# USB_IFC.net
KiCad netlist of a schematic drawn in Altium Designer
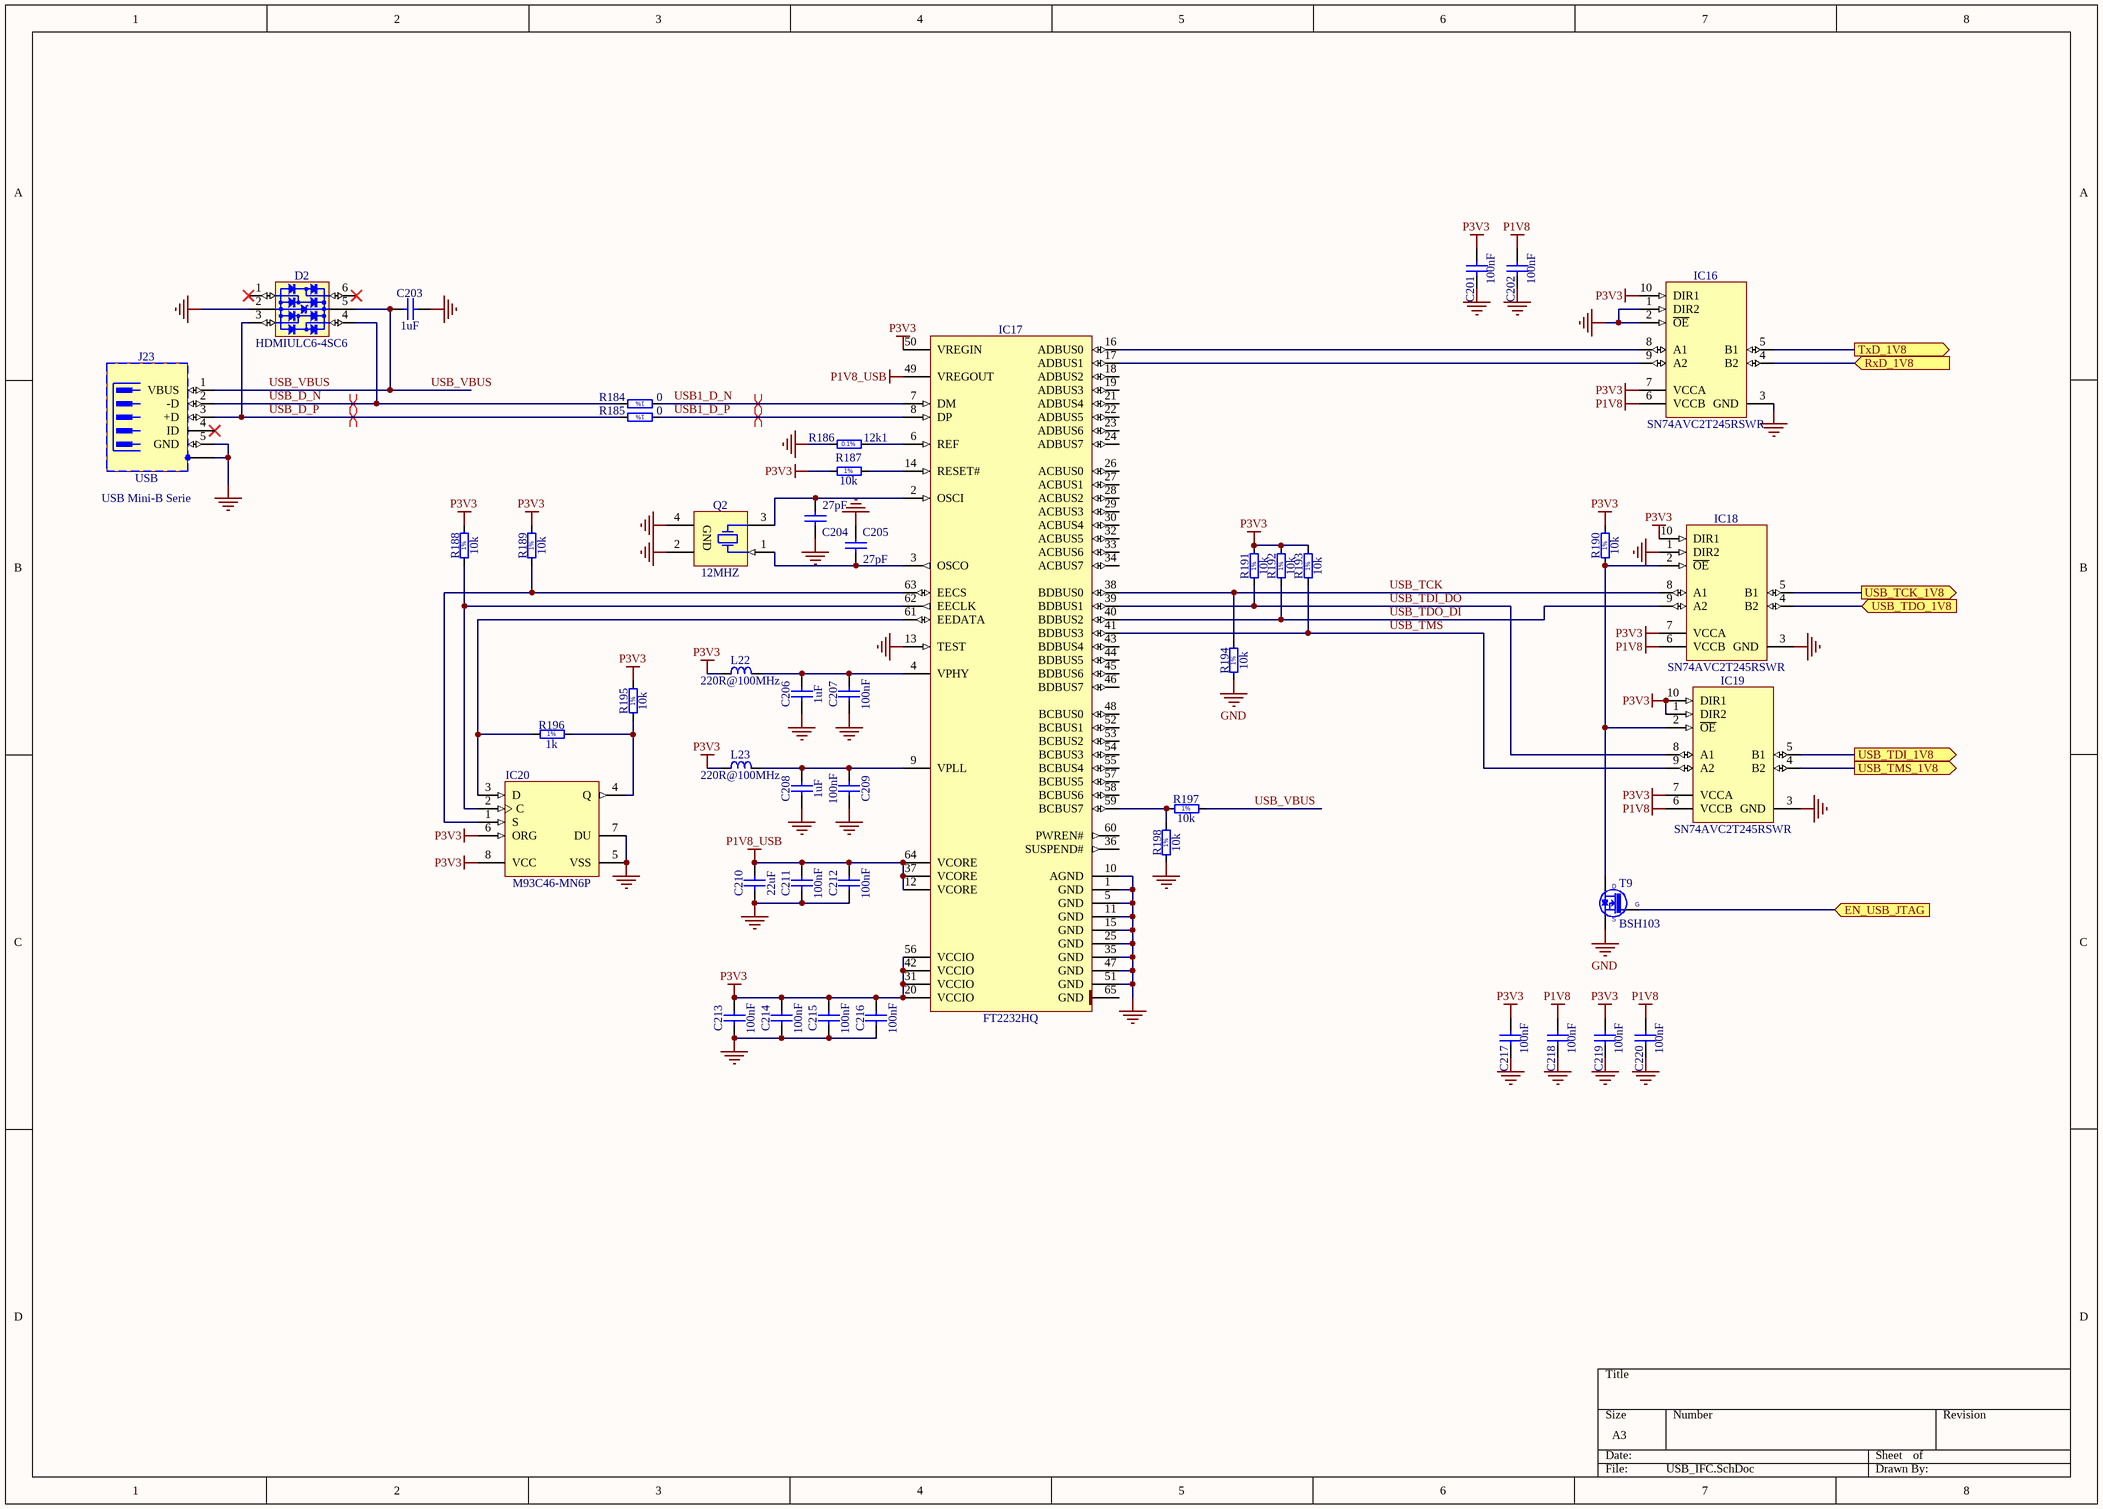
[diagram p0: USB_IFC.SchDoc]

(export (version "E")
  (design (tool "Eeschema 10.0.6"))
  (components
    (comp (ref "C201")
      (value "100nF")
      (footprint "CAPC0603X33N")
      (description "Non-polarised capacitor")
      (fields
        (field (name "PART NUMBER") "CC0201_100NF_6.3V_10%_X5R")
        (field (name "VOLTAGE") "6.3V")
        (field (name "AUTHOR") "CERN DEM JLC")
      )
      (libsource (lib "Capacitors") (part "Capacitor - non polarized"))
    )
    (comp (ref "C202")
      (value "100nF")
      (footprint "CAPC0603X33N")
      (description "Non-polarised capacitor")
      (fields
        (field (name "PART NUMBER") "CC0201_100NF_6.3V_10%_X5R")
        (field (name "VOLTAGE") "6.3V")
        (field (name "AUTHOR") "CERN DEM JLC")
      )
      (libsource (lib "Capacitors") (part "Capacitor - non polarized"))
    )
    (comp (ref "C203")
      (value "1uF")
      (footprint "CAPC1005X55N")
      (description "Non-polarised capacitor")
      (fields
        (field (name "PART NUMBER") "CC0402_1UF_16V_10%_X5R")
        (field (name "VOLTAGE") "16V")
        (field (name "AUTHOR") "CERN DEM JLC")
      )
      (libsource (lib "Capacitors") (part "Capacitor - non polarized"))
    )
    (comp (ref "C204")
      (value "27pF")
      (footprint "CAPC1608X87N")
      (description "Non-polarised capacitor")
      (fields
        (field (name "PART NUMBER") "CC0603_27PF_50V_5%_NP0")
        (field (name "VOLTAGE") "50V")
        (field (name "AUTHOR") "CERN DEM JLC")
      )
      (libsource (lib "Capacitors") (part "Capacitor - non polarized"))
    )
    (comp (ref "C205")
      (value "27pF")
      (footprint "CAPC1608X87N")
      (description "Non-polarised capacitor")
      (fields
        (field (name "PART NUMBER") "CC0603_27PF_50V_5%_NP0")
        (field (name "VOLTAGE") "50V")
        (field (name "AUTHOR") "CERN DEM JLC")
      )
      (libsource (lib "Capacitors") (part "Capacitor - non polarized"))
    )
    (comp (ref "C206")
      (value "1uF")
      (footprint "CAPC1005X55N")
      (description "Non-polarised capacitor")
      (fields
        (field (name "PART NUMBER") "CC0402_1UF_16V_10%_X5R")
        (field (name "VOLTAGE") "16V")
        (field (name "AUTHOR") "CERN DEM JLC")
      )
      (libsource (lib "Capacitors") (part "Capacitor - non polarized"))
    )
    (comp (ref "C207")
      (value "100nF")
      (footprint "CAPC0603X33N")
      (description "Non-polarised capacitor")
      (fields
        (field (name "PART NUMBER") "CC0201_100NF_6.3V_10%_X5R")
        (field (name "VOLTAGE") "6.3V")
        (field (name "AUTHOR") "CERN DEM JLC")
      )
      (libsource (lib "Capacitors") (part "Capacitor - non polarized"))
    )
    (comp (ref "C208")
      (value "1uF")
      (footprint "CAPC1005X55N")
      (description "Non-polarised capacitor")
      (fields
        (field (name "PART NUMBER") "CC0402_1UF_16V_10%_X5R")
        (field (name "VOLTAGE") "16V")
        (field (name "AUTHOR") "CERN DEM JLC")
      )
      (libsource (lib "Capacitors") (part "Capacitor - non polarized"))
    )
    (comp (ref "C209")
      (value "100nF")
      (footprint "CAPC0603X33N")
      (description "Non-polarised capacitor")
      (fields
        (field (name "PART NUMBER") "CC0201_100NF_6.3V_10%_X5R")
        (field (name "VOLTAGE") "6.3V")
        (field (name "AUTHOR") "CERN DEM JLC")
      )
      (libsource (lib "Capacitors") (part "Capacitor - non polarized"))
    )
    (comp (ref "C210")
      (value "22uF")
      (footprint "CAPC2012X135N")
      (description "Non-polarised capacitor")
      (fields
        (field (name "PART NUMBER") "CC0805_22UF_6.3V_20%_X5R")
        (field (name "VOLTAGE") "6.3V")
        (field (name "AUTHOR") "CERN DEM JLC")
      )
      (libsource (lib "Capacitors") (part "Capacitor - non polarized"))
    )
    (comp (ref "C211")
      (value "100nF")
      (footprint "CAPC0603X33N")
      (description "Non-polarised capacitor")
      (fields
        (field (name "PART NUMBER") "CC0201_100NF_6.3V_10%_X5R")
        (field (name "VOLTAGE") "6.3V")
        (field (name "AUTHOR") "CERN DEM JLC")
      )
      (libsource (lib "Capacitors") (part "Capacitor - non polarized"))
    )
    (comp (ref "C212")
      (value "100nF")
      (footprint "CAPC0603X33N")
      (description "Non-polarised capacitor")
      (fields
        (field (name "PART NUMBER") "CC0201_100NF_6.3V_10%_X5R")
        (field (name "VOLTAGE") "6.3V")
        (field (name "AUTHOR") "CERN DEM JLC")
      )
      (libsource (lib "Capacitors") (part "Capacitor - non polarized"))
    )
    (comp (ref "C213")
      (value "100nF")
      (footprint "CAPC0603X33N")
      (description "Non-polarised capacitor")
      (fields
        (field (name "PART NUMBER") "CC0201_100NF_6.3V_10%_X5R")
        (field (name "VOLTAGE") "6.3V")
        (field (name "AUTHOR") "CERN DEM JLC")
      )
      (libsource (lib "Capacitors") (part "Capacitor - non polarized"))
    )
    (comp (ref "C214")
      (value "100nF")
      (footprint "CAPC0603X33N")
      (description "Non-polarised capacitor")
      (fields
        (field (name "PART NUMBER") "CC0201_100NF_6.3V_10%_X5R")
        (field (name "VOLTAGE") "6.3V")
        (field (name "AUTHOR") "CERN DEM JLC")
      )
      (libsource (lib "Capacitors") (part "Capacitor - non polarized"))
    )
    (comp (ref "C215")
      (value "100nF")
      (footprint "CAPC0603X33N")
      (description "Non-polarised capacitor")
      (fields
        (field (name "PART NUMBER") "CC0201_100NF_6.3V_10%_X5R")
        (field (name "VOLTAGE") "6.3V")
        (field (name "AUTHOR") "CERN DEM JLC")
      )
      (libsource (lib "Capacitors") (part "Capacitor - non polarized"))
    )
    (comp (ref "C216")
      (value "100nF")
      (footprint "CAPC0603X33N")
      (description "Non-polarised capacitor")
      (fields
        (field (name "PART NUMBER") "CC0201_100NF_6.3V_10%_X5R")
        (field (name "VOLTAGE") "6.3V")
        (field (name "AUTHOR") "CERN DEM JLC")
      )
      (libsource (lib "Capacitors") (part "Capacitor - non polarized"))
    )
    (comp (ref "C217")
      (value "100nF")
      (footprint "CAPC0603X33N")
      (description "Non-polarised capacitor")
      (fields
        (field (name "PART NUMBER") "CC0201_100NF_6.3V_10%_X5R")
        (field (name "VOLTAGE") "6.3V")
        (field (name "AUTHOR") "CERN DEM JLC")
      )
      (libsource (lib "Capacitors") (part "Capacitor - non polarized"))
    )
    (comp (ref "C218")
      (value "100nF")
      (footprint "CAPC0603X33N")
      (description "Non-polarised capacitor")
      (fields
        (field (name "PART NUMBER") "CC0201_100NF_6.3V_10%_X5R")
        (field (name "VOLTAGE") "6.3V")
        (field (name "AUTHOR") "CERN DEM JLC")
      )
      (libsource (lib "Capacitors") (part "Capacitor - non polarized"))
    )
    (comp (ref "C219")
      (value "100nF")
      (footprint "CAPC0603X33N")
      (description "Non-polarised capacitor")
      (fields
        (field (name "PART NUMBER") "CC0201_100NF_6.3V_10%_X5R")
        (field (name "VOLTAGE") "6.3V")
        (field (name "AUTHOR") "CERN DEM JLC")
      )
      (libsource (lib "Capacitors") (part "Capacitor - non polarized"))
    )
    (comp (ref "C220")
      (value "100nF")
      (footprint "CAPC0603X33N")
      (description "Non-polarised capacitor")
      (fields
        (field (name "PART NUMBER") "CC0201_100NF_6.3V_10%_X5R")
        (field (name "VOLTAGE") "6.3V")
        (field (name "AUTHOR") "CERN DEM JLC")
      )
      (libsource (lib "Capacitors") (part "Capacitor - non polarized"))
    )
    (comp (ref "D2")
      (value "HDMIULC6-4SC6")
      (footprint "SOT95P280X145-6N")
      (description "Ultra Large Bandwidth HDMI ESD Protection")
      (fields
        (field (name "VOLTAGE") "6V")
        (field (name "MANUFACTURER") "ST MICROELECTRONICS")
        (field (name "AUTHOR") "CERN DEM JLC")
      )
      (libsource (lib "ICs And Semiconductors") (part "HDMIULC6-4SC6"))
    )
    (comp (ref "IC16")
      (value "SN74AVC2T245RSWR")
      (footprint "QFN40P140X180X55-10N")
      (description "Dual-Bit Dual-Supply Bus Transceiver With Configurable Voltage Translation and 3-State Outputs")
      (fields (field (name "MANUFACTURER") "TEXAS INSTRUMENTS") (field (name "AUTHOR") "CERN DEM JLC"))
      (libsource (lib "ICs And Semiconductors") (part "742T245"))
    )
    (comp (ref "IC17")
      (value "FT2232HQ")
      (footprint "QFN50P900X900X100-65N-S445")
      (description "Dual High Speed USB To Multipurpose UART/FIFO IC, 64-pin QFN, Tray")
      (fields
        (field (name "MANUFACTURER") "FUTURE TECHNOLOGY DEVICES INTERNATIONAL (FTDI)")
        (field (name "AUTHOR") "CERN DEM JLC")
      )
      (libsource (lib "ICs And Semiconductors") (part "FT2232HQ"))
    )
    (comp (ref "IC18")
      (value "SN74AVC2T245RSWR")
      (footprint "QFN40P140X180X55-10N")
      (description "Dual-Bit Dual-Supply Bus Transceiver With Configurable Voltage Translation and 3-State Outputs")
      (fields (field (name "MANUFACTURER") "TEXAS INSTRUMENTS") (field (name "AUTHOR") "CERN DEM JLC"))
      (libsource (lib "ICs And Semiconductors") (part "742T245"))
    )
    (comp (ref "IC19")
      (value "SN74AVC2T245RSWR")
      (footprint "QFN40P140X180X55-10N")
      (description "Dual-Bit Dual-Supply Bus Transceiver With Configurable Voltage Translation and 3-State Outputs")
      (fields (field (name "MANUFACTURER") "TEXAS INSTRUMENTS") (field (name "AUTHOR") "CERN DEM JLC"))
      (libsource (lib "ICs And Semiconductors") (part "742T245"))
    )
    (comp (ref "IC20")
      (value "M93C46-MN6P")
      (footprint "SOIC127P600X175-8N")
      (description "1Kb (x8/x16) Serial Microwire Bus EEPROM")
      (fields (field (name "MANUFACTURER") "ST MICROELECTRONICS") (field (name "AUTHOR") "CERN DEM JLC"))
      (libsource (lib "ICs And Semiconductors") (part "M93C46-MN"))
    )
    (comp (ref "J23")
      (value "USB")
      (footprint "WURTH_651005136521")
      (description "5 Pin + 1 Shield USB Receptacle")
      (fields
        (field (name "PART NUMBER") "WURTH_651005136521")
        (field (name "MANUFACTURER") "WURTH ELEKTRONIK")
        (field (name "AUTHOR") "CERN DEM JLC")
      )
      (libsource (lib "Connectors") (part "Connector USB 5 Pin + 1Shield"))
    )
    (comp (ref "L22")
      (value "220R@100MHz")
      (footprint "INDC2012X105N")
      (description "Inductor")
      (fields
        (field (name "PART NUMBER") "IND0805_MURATA_BLM21PG221SN1D")
        (field (name "POWER") "2A")
        (field (name "AUTHOR") "CERN DEM JLC")
      )
      (libsource (lib "Inductors & Transformers") (part "Inductor"))
    )
    (comp (ref "L23")
      (value "220R@100MHz")
      (footprint "INDC2012X105N")
      (description "Inductor")
      (fields
        (field (name "PART NUMBER") "IND0805_MURATA_BLM21PG221SN1D")
        (field (name "POWER") "2A")
        (field (name "AUTHOR") "CERN DEM JLC")
      )
      (libsource (lib "Inductors & Transformers") (part "Inductor"))
    )
    (comp (ref "Q2")
      (value "12MHZ")
      (footprint "XTAL_ABRACON_ABM3B")
      (description "Crystal 4 pins 1=XTAL Control 2=GND3=XTAL 4=GND")
      (fields
        (field (name "PART NUMBER") "XTAL_12MHZ_ABRACON_ABM3B-12.000MHZ-B2-T")
        (field (name "MANUFACTURER") "ABRACON")
        (field (name "AUTHOR") "CERN DEM JLC")
      )
      (libsource (lib "ICs And Semiconductors") (part "Quartz Crystal 1X 2GND 3X 4GND"))
    )
    (comp (ref "R184")
      (value "0")
      (footprint "RESC1608X55N")
      (description "Resistor - 1%")
      (fields
        (field (name "PART NUMBER") "R0603_0R_JUMPER")
        (field (name "MANUFACTURER") "GENERIC")
        (field (name "AUTHOR") "CERN DEM JLC")
      )
      (libsource (lib "Resistors") (part "Resistor - 1%"))
    )
    (comp (ref "R185")
      (value "0")
      (footprint "RESC1608X55N")
      (description "Resistor - 1%")
      (fields
        (field (name "PART NUMBER") "R0603_0R_JUMPER")
        (field (name "MANUFACTURER") "GENERIC")
        (field (name "AUTHOR") "CERN DEM JLC")
      )
      (libsource (lib "Resistors") (part "Resistor - 1%"))
    )
    (comp (ref "R186")
      (value "12k1")
      (footprint "RESC1608X55N")
      (description "Resistor - 0.1%")
      (fields
        (field (name "PART NUMBER") "R0603_12K1_0.1%_0.063W_10PPM")
        (field (name "POWER") "0.063W")
        (field (name "AUTHOR") "CERN DEM JLC")
      )
      (libsource (lib "Resistors") (part "Resistor - 0.1%"))
    )
    (comp (ref "R187")
      (value "10k")
      (footprint "RESC1005X40N")
      (description "Resistor - 1%")
      (fields
        (field (name "PART NUMBER") "R0402_10K_1%_0.0625W_100PPM")
        (field (name "POWER") "0.0625W")
        (field (name "AUTHOR") "CERN DEM JLC")
      )
      (libsource (lib "Resistors") (part "Resistor - 1%"))
    )
    (comp (ref "R188")
      (value "10k")
      (footprint "RESC1005X40N")
      (description "Resistor - 1%")
      (fields
        (field (name "PART NUMBER") "R0402_10K_1%_0.0625W_100PPM")
        (field (name "POWER") "0.0625W")
        (field (name "AUTHOR") "CERN DEM JLC")
      )
      (libsource (lib "Resistors") (part "Resistor - 1%"))
    )
    (comp (ref "R189")
      (value "10k")
      (footprint "RESC1005X40N")
      (description "Resistor - 1%")
      (fields
        (field (name "PART NUMBER") "R0402_10K_1%_0.0625W_100PPM")
        (field (name "POWER") "0.0625W")
        (field (name "AUTHOR") "CERN DEM JLC")
      )
      (libsource (lib "Resistors") (part "Resistor - 1%"))
    )
    (comp (ref "R190")
      (value "10k")
      (footprint "RESC1005X40N")
      (description "Resistor - 1%")
      (fields
        (field (name "PART NUMBER") "R0402_10K_1%_0.0625W_100PPM")
        (field (name "POWER") "0.0625W")
        (field (name "AUTHOR") "CERN DEM JLC")
      )
      (libsource (lib "Resistors") (part "Resistor - 1%"))
    )
    (comp (ref "R191")
      (value "10k")
      (footprint "RESC1005X40N")
      (description "Resistor - 1%")
      (fields
        (field (name "PART NUMBER") "R0402_10K_1%_0.0625W_100PPM")
        (field (name "POWER") "0.0625W")
        (field (name "AUTHOR") "CERN DEM JLC")
      )
      (libsource (lib "Resistors") (part "Resistor - 1%"))
    )
    (comp (ref "R192")
      (value "10k")
      (footprint "RESC1005X40N")
      (description "Resistor - 1%")
      (fields
        (field (name "PART NUMBER") "R0402_10K_1%_0.0625W_100PPM")
        (field (name "POWER") "0.0625W")
        (field (name "AUTHOR") "CERN DEM JLC")
      )
      (libsource (lib "Resistors") (part "Resistor - 1%"))
    )
    (comp (ref "R193")
      (value "10k")
      (footprint "RESC1005X40N")
      (description "Resistor - 1%")
      (fields
        (field (name "PART NUMBER") "R0402_10K_1%_0.0625W_100PPM")
        (field (name "POWER") "0.0625W")
        (field (name "AUTHOR") "CERN DEM JLC")
      )
      (libsource (lib "Resistors") (part "Resistor - 1%"))
    )
    (comp (ref "R194")
      (value "10k")
      (footprint "RESC1005X40N")
      (description "Resistor - 1%")
      (fields
        (field (name "PART NUMBER") "R0402_10K_1%_0.0625W_100PPM")
        (field (name "POWER") "0.0625W")
        (field (name "AUTHOR") "CERN DEM JLC")
      )
      (libsource (lib "Resistors") (part "Resistor - 1%"))
    )
    (comp (ref "R195")
      (value "10k")
      (footprint "RESC1005X40N")
      (description "Resistor - 1%")
      (fields
        (field (name "PART NUMBER") "R0402_10K_1%_0.0625W_100PPM")
        (field (name "POWER") "0.0625W")
        (field (name "AUTHOR") "CERN DEM JLC")
      )
      (libsource (lib "Resistors") (part "Resistor - 1%"))
    )
    (comp (ref "R196")
      (value "1k")
      (footprint "RESC1005X40N")
      (description "Resistor - 1%")
      (fields
        (field (name "PART NUMBER") "R0402_1K_1%_0.0625W_100PPM")
        (field (name "POWER") "0.0625W")
        (field (name "AUTHOR") "CERN DEM JLC")
      )
      (libsource (lib "Resistors") (part "Resistor - 1%"))
    )
    (comp (ref "R197")
      (value "10k")
      (footprint "RESC1005X40N")
      (description "Resistor - 1%")
      (fields
        (field (name "PART NUMBER") "R0402_10K_1%_0.0625W_100PPM")
        (field (name "POWER") "0.0625W")
        (field (name "AUTHOR") "CERN DEM JLC")
      )
      (libsource (lib "Resistors") (part "Resistor - 1%"))
    )
    (comp (ref "R198")
      (value "10k")
      (footprint "RESC1005X40N")
      (description "Resistor - 1%")
      (fields
        (field (name "PART NUMBER") "R0402_10K_1%_0.0625W_100PPM")
        (field (name "POWER") "0.0625W")
        (field (name "AUTHOR") "CERN DEM JLC")
      )
      (libsource (lib "Resistors") (part "Resistor - 1%"))
    )
    (comp (ref "T9")
      (value "BSH103")
      (footprint "SOT95P230X110-3N")
      (description "N-CHANNEL MOSFET WITH DIODE")
      (fields (field (name "MANUFACTURER") "NEXPERIA") (field (name "AUTHOR") "CERN DEM JLC"))
      (libsource (lib "ICs And Semiconductors") (part "N-MOSFET-D 1G 2S 3D"))
    )
  )
  (nets
    (net (code "1") (name "/EN_USB_JTAG") (class "Default")
      (node (ref "T9") (pin "1") (pinfunction "G_1") (pintype "passive"))
    )
    (net (code "2") (name "/RxD_1V8") (class "Default")
      (node (ref "IC16") (pin "4") (pinfunction "B2_4") (pintype "bidirectional"))
    )
    (net (code "3") (name "/TxD_1V8") (class "Default")
      (node (ref "IC16") (pin "5") (pinfunction "B1_5") (pintype "bidirectional"))
    )
    (net (code "4") (name "/USB1_D_N") (class "Default")
      (node (ref "IC17") (pin "7") (pinfunction "DM_7") (pintype "input"))
      (node (ref "R184") (pin "1") (pinfunction "1_1") (pintype "passive"))
    )
    (net (code "5") (name "/USB1_D_P") (class "Default")
      (node (ref "IC17") (pin "8") (pinfunction "DP_8") (pintype "input"))
      (node (ref "R185") (pin "1") (pinfunction "1_1") (pintype "passive"))
    )
    (net (code "6") (name "/USB_D_N") (class "Default")
      (node (ref "D2") (pin "4") (pinfunction "I/O3_4") (pintype "bidirectional"))
      (node (ref "J23") (pin "2") (pinfunction "-D_2") (pintype "bidirectional"))
      (node (ref "R184") (pin "2") (pinfunction "2_2") (pintype "passive"))
    )
    (net (code "7") (name "/USB_D_P") (class "Default")
      (node (ref "D2") (pin "3") (pinfunction "I/O2_3") (pintype "bidirectional"))
      (node (ref "J23") (pin "3") (pinfunction "+D_3") (pintype "bidirectional"))
      (node (ref "R185") (pin "2") (pinfunction "2_2") (pintype "passive"))
    )
    (net (code "8") (name "/USB_TCK") (class "Default")
      (node (ref "IC17") (pin "38") (pinfunction "BDBUS0_38") (pintype "bidirectional"))
      (node (ref "IC18") (pin "8") (pinfunction "A1_8") (pintype "bidirectional"))
      (node (ref "R194") (pin "2") (pinfunction "2_2") (pintype "passive"))
    )
    (net (code "9") (name "/USB_TCK_1V8") (class "Default")
      (node (ref "IC18") (pin "5") (pinfunction "B1_5") (pintype "bidirectional"))
    )
    (net (code "10") (name "/USB_TDI_1V8") (class "Default")
      (node (ref "IC19") (pin "5") (pinfunction "B1_5") (pintype "bidirectional"))
    )
    (net (code "11") (name "/USB_TDI_DO") (class "Default")
      (node (ref "IC17") (pin "39") (pinfunction "BDBUS1_39") (pintype "bidirectional"))
      (node (ref "IC19") (pin "8") (pinfunction "A1_8") (pintype "bidirectional"))
      (node (ref "R191") (pin "1") (pinfunction "1_1") (pintype "passive"))
    )
    (net (code "12") (name "/USB_TDO_1V8") (class "Default")
      (node (ref "IC18") (pin "4") (pinfunction "B2_4") (pintype "bidirectional"))
    )
    (net (code "13") (name "/USB_TDO_DI") (class "Default")
      (node (ref "IC17") (pin "40") (pinfunction "BDBUS2_40") (pintype "bidirectional"))
      (node (ref "IC18") (pin "9") (pinfunction "A2_9") (pintype "bidirectional"))
      (node (ref "R192") (pin "1") (pinfunction "1_1") (pintype "passive"))
    )
    (net (code "14") (name "/USB_TMS") (class "Default")
      (node (ref "IC17") (pin "41") (pinfunction "BDBUS3_41") (pintype "bidirectional"))
      (node (ref "IC19") (pin "9") (pinfunction "A2_9") (pintype "bidirectional"))
      (node (ref "R193") (pin "1") (pinfunction "1_1") (pintype "passive"))
    )
    (net (code "15") (name "/USB_TMS_1V8") (class "Default")
      (node (ref "IC19") (pin "4") (pinfunction "B2_4") (pintype "bidirectional"))
    )
    (net (code "16") (name "/USB_VBUS") (class "Default")
      (node (ref "C203") (pin "1") (pinfunction "1_1") (pintype "passive"))
      (node (ref "D2") (pin "5") (pinfunction "VBUS_5") (pintype "power_in"))
      (node (ref "J23") (pin "1") (pinfunction "VBUS_1") (pintype "bidirectional"))
      (node (ref "R197") (pin "2") (pinfunction "2_2") (pintype "passive"))
    )
    (net (code "17") (name "GND") (class "Default")
      (node (ref "C201") (pin "1") (pinfunction "1_1") (pintype "passive"))
      (node (ref "C202") (pin "1") (pinfunction "1_1") (pintype "passive"))
      (node (ref "C203") (pin "2") (pinfunction "2_2") (pintype "passive"))
      (node (ref "C204") (pin "2") (pinfunction "2_2") (pintype "passive"))
      (node (ref "C205") (pin "1") (pinfunction "1_1") (pintype "passive"))
      (node (ref "C206") (pin "1") (pinfunction "1_1") (pintype "passive"))
      (node (ref "C207") (pin "1") (pinfunction "1_1") (pintype "passive"))
      (node (ref "C208") (pin "1") (pinfunction "1_1") (pintype "passive"))
      (node (ref "C209") (pin "2") (pinfunction "2_2") (pintype "passive"))
      (node (ref "C210") (pin "1") (pinfunction "1_1") (pintype "passive"))
      (node (ref "C211") (pin "1") (pinfunction "1_1") (pintype "passive"))
      (node (ref "C212") (pin "1") (pinfunction "1_1") (pintype "passive"))
      (node (ref "C213") (pin "1") (pinfunction "1_1") (pintype "passive"))
      (node (ref "C214") (pin "1") (pinfunction "1_1") (pintype "passive"))
      (node (ref "C215") (pin "1") (pinfunction "1_1") (pintype "passive"))
      (node (ref "C216") (pin "1") (pinfunction "1_1") (pintype "passive"))
      (node (ref "C217") (pin "1") (pinfunction "1_1") (pintype "passive"))
      (node (ref "C218") (pin "1") (pinfunction "1_1") (pintype "passive"))
      (node (ref "C219") (pin "1") (pinfunction "1_1") (pintype "passive"))
      (node (ref "C220") (pin "1") (pinfunction "1_1") (pintype "passive"))
      (node (ref "D2") (pin "2") (pinfunction "GND_2") (pintype "power_in"))
      (node (ref "IC16") (pin "1") (pinfunction "DIR2_1") (pintype "input"))
      (node (ref "IC16") (pin "2") (pinfunction "~{OE}_2") (pintype "input"))
      (node (ref "IC16") (pin "3") (pinfunction "GND_3") (pintype "power_in"))
      (node (ref "IC17") (pin "1") (pinfunction "GND_1") (pintype "power_in"))
      (node (ref "IC17") (pin "10") (pinfunction "AGND_10") (pintype "power_in"))
      (node (ref "IC17") (pin "11") (pinfunction "GND_11") (pintype "power_in"))
      (node (ref "IC17") (pin "13") (pinfunction "TEST_13") (pintype "input"))
      (node (ref "IC17") (pin "15") (pinfunction "GND_15") (pintype "power_in"))
      (node (ref "IC17") (pin "25") (pinfunction "GND_25") (pintype "power_in"))
      (node (ref "IC17") (pin "35") (pinfunction "GND_35") (pintype "power_in"))
      (node (ref "IC17") (pin "47") (pinfunction "GND_47") (pintype "power_in"))
      (node (ref "IC17") (pin "5") (pinfunction "GND_5") (pintype "power_in"))
      (node (ref "IC17") (pin "51") (pinfunction "GND_51") (pintype "power_in"))
      (node (ref "IC18") (pin "1") (pinfunction "DIR2_1") (pintype "input"))
      (node (ref "IC18") (pin "3") (pinfunction "GND_3") (pintype "power_in"))
      (node (ref "IC19") (pin "3") (pinfunction "GND_3") (pintype "power_in"))
      (node (ref "IC20") (pin "5") (pinfunction "VSS_5") (pintype "power_in"))
      (node (ref "IC20") (pin "7") (pinfunction "DU_7") (pintype "passive"))
      (node (ref "J23") (pin "5") (pinfunction "GND_5") (pintype "bidirectional"))
      (node (ref "J23") (pin "6") (pinfunction "SH_6") (pintype "power_in"))
      (node (ref "Q2") (pin "2") (pinfunction "GND_2") (pintype "power_in"))
      (node (ref "Q2") (pin "4") (pinfunction "GND_4") (pintype "power_in"))
      (node (ref "R186") (pin "1") (pinfunction "1_1") (pintype "passive"))
      (node (ref "R194") (pin "1") (pinfunction "1_1") (pintype "passive"))
      (node (ref "R198") (pin "1") (pinfunction "1_1") (pintype "passive"))
      (node (ref "T9") (pin "2") (pinfunction "S_2") (pintype "passive"))
    )
    (net (code "18") (name "Net-(IC16-A1)") (class "Default")
      (node (ref "IC16") (pin "8") (pinfunction "A1_8") (pintype "bidirectional"))
      (node (ref "IC17") (pin "16") (pinfunction "ADBUS0_16") (pintype "bidirectional"))
    )
    (net (code "19") (name "Net-(IC16-A2)") (class "Default")
      (node (ref "IC16") (pin "9") (pinfunction "A2_9") (pintype "bidirectional"))
      (node (ref "IC17") (pin "17") (pinfunction "ADBUS1_17") (pintype "bidirectional"))
    )
    (net (code "20") (name "Net-(IC17-BCBUS7)") (class "Default")
      (node (ref "IC17") (pin "59") (pinfunction "BCBUS7_59") (pintype "bidirectional"))
      (node (ref "R197") (pin "1") (pinfunction "1_1") (pintype "passive"))
      (node (ref "R198") (pin "2") (pinfunction "2_2") (pintype "passive"))
    )
    (net (code "21") (name "Net-(IC17-EECLK)") (class "Default")
      (node (ref "IC17") (pin "62") (pinfunction "EECLK_62") (pintype "output"))
      (node (ref "IC20") (pin "2") (pinfunction "C_2") (pintype "input"))
      (node (ref "R188") (pin "1") (pinfunction "1_1") (pintype "passive"))
    )
    (net (code "22") (name "Net-(IC17-EECS)") (class "Default")
      (node (ref "IC17") (pin "63") (pinfunction "EECS_63") (pintype "bidirectional"))
      (node (ref "IC20") (pin "1") (pinfunction "S_1") (pintype "input"))
      (node (ref "R189") (pin "1") (pinfunction "1_1") (pintype "passive"))
    )
    (net (code "23") (name "Net-(IC17-EEDATA)") (class "Default")
      (node (ref "IC17") (pin "61") (pinfunction "EEDATA_61") (pintype "bidirectional"))
      (node (ref "IC20") (pin "3") (pinfunction "D_3") (pintype "input"))
      (node (ref "R196") (pin "1") (pinfunction "1_1") (pintype "passive"))
    )
    (net (code "24") (name "Net-(IC17-OSCI)") (class "Default")
      (node (ref "C204") (pin "1") (pinfunction "1_1") (pintype "passive"))
      (node (ref "IC17") (pin "2") (pinfunction "OSCI_2") (pintype "input"))
      (node (ref "Q2") (pin "3") (pinfunction "X_3") (pintype "power_in"))
    )
    (net (code "25") (name "Net-(IC17-OSCO)") (class "Default")
      (node (ref "C205") (pin "2") (pinfunction "2_2") (pintype "passive"))
      (node (ref "IC17") (pin "3") (pinfunction "OSCO_3") (pintype "output"))
      (node (ref "Q2") (pin "1") (pinfunction "X_1") (pintype "input"))
    )
    (net (code "26") (name "Net-(IC17-REF)") (class "Default")
      (node (ref "IC17") (pin "6") (pinfunction "REF_6") (pintype "input"))
      (node (ref "R186") (pin "2") (pinfunction "2_2") (pintype "passive"))
    )
    (net (code "27") (name "Net-(IC17-RESET#)") (class "Default")
      (node (ref "IC17") (pin "14") (pinfunction "RESET#_14") (pintype "input"))
      (node (ref "R187") (pin "2") (pinfunction "2_2") (pintype "passive"))
    )
    (net (code "28") (name "Net-(IC17-VPHY)") (class "Default")
      (node (ref "C206") (pin "2") (pinfunction "2_2") (pintype "passive"))
      (node (ref "C207") (pin "2") (pinfunction "2_2") (pintype "passive"))
      (node (ref "IC17") (pin "4") (pinfunction "VPHY_4") (pintype "power_in"))
      (node (ref "L22") (pin "2") (pinfunction "2_2") (pintype "passive"))
    )
    (net (code "29") (name "Net-(IC17-VPLL)") (class "Default")
      (node (ref "C208") (pin "2") (pinfunction "2_2") (pintype "passive"))
      (node (ref "C209") (pin "1") (pinfunction "1_1") (pintype "passive"))
      (node (ref "IC17") (pin "9") (pinfunction "VPLL_9") (pintype "power_in"))
      (node (ref "L23") (pin "2") (pinfunction "2_2") (pintype "passive"))
    )
    (net (code "30") (name "Net-(IC18-~{OE})") (class "Default")
      (node (ref "IC18") (pin "2") (pinfunction "~{OE}_2") (pintype "input"))
      (node (ref "IC19") (pin "2") (pinfunction "~{OE}_2") (pintype "input"))
      (node (ref "R190") (pin "1") (pinfunction "1_1") (pintype "passive"))
      (node (ref "T9") (pin "3") (pinfunction "D_3") (pintype "passive"))
    )
    (net (code "31") (name "Net-(IC20-Q)") (class "Default")
      (node (ref "IC20") (pin "4") (pinfunction "Q_4") (pintype "output"))
      (node (ref "R195") (pin "1") (pinfunction "1_1") (pintype "passive"))
      (node (ref "R196") (pin "2") (pinfunction "2_2") (pintype "passive"))
    )
    (net (code "32") (name "P1V8") (class "Default")
      (node (ref "C202") (pin "2") (pinfunction "2_2") (pintype "passive"))
      (node (ref "C218") (pin "2") (pinfunction "2_2") (pintype "passive"))
      (node (ref "C220") (pin "2") (pinfunction "2_2") (pintype "passive"))
      (node (ref "IC16") (pin "6") (pinfunction "VCCB_6") (pintype "power_in"))
      (node (ref "IC18") (pin "6") (pinfunction "VCCB_6") (pintype "power_in"))
      (node (ref "IC19") (pin "6") (pinfunction "VCCB_6") (pintype "power_in"))
    )
    (net (code "33") (name "P1V8_USB") (class "Default")
      (node (ref "C210") (pin "2") (pinfunction "2_2") (pintype "passive"))
      (node (ref "C211") (pin "2") (pinfunction "2_2") (pintype "passive"))
      (node (ref "C212") (pin "2") (pinfunction "2_2") (pintype "passive"))
      (node (ref "IC17") (pin "12") (pinfunction "VCORE_12") (pintype "power_in"))
      (node (ref "IC17") (pin "37") (pinfunction "VCORE_37") (pintype "power_in"))
      (node (ref "IC17") (pin "49") (pinfunction "VREGOUT_49") (pintype "power_in"))
      (node (ref "IC17") (pin "64") (pinfunction "VCORE_64") (pintype "power_in"))
    )
    (net (code "34") (name "P3V3") (class "Default")
      (node (ref "C201") (pin "2") (pinfunction "2_2") (pintype "passive"))
      (node (ref "C213") (pin "2") (pinfunction "2_2") (pintype "passive"))
      (node (ref "C214") (pin "2") (pinfunction "2_2") (pintype "passive"))
      (node (ref "C215") (pin "2") (pinfunction "2_2") (pintype "passive"))
      (node (ref "C216") (pin "2") (pinfunction "2_2") (pintype "passive"))
      (node (ref "C217") (pin "2") (pinfunction "2_2") (pintype "passive"))
      (node (ref "C219") (pin "2") (pinfunction "2_2") (pintype "passive"))
      (node (ref "IC16") (pin "10") (pinfunction "DIR1_10") (pintype "input"))
      (node (ref "IC16") (pin "7") (pinfunction "VCCA_7") (pintype "power_in"))
      (node (ref "IC17") (pin "20") (pinfunction "VCCIO_20") (pintype "power_in"))
      (node (ref "IC17") (pin "31") (pinfunction "VCCIO_31") (pintype "power_in"))
      (node (ref "IC17") (pin "42") (pinfunction "VCCIO_42") (pintype "power_in"))
      (node (ref "IC17") (pin "50") (pinfunction "VREGIN_50") (pintype "power_in"))
      (node (ref "IC17") (pin "56") (pinfunction "VCCIO_56") (pintype "power_in"))
      (node (ref "IC18") (pin "10") (pinfunction "DIR1_10") (pintype "input"))
      (node (ref "IC18") (pin "7") (pinfunction "VCCA_7") (pintype "power_in"))
      (node (ref "IC19") (pin "1") (pinfunction "DIR2_1") (pintype "input"))
      (node (ref "IC19") (pin "10") (pinfunction "DIR1_10") (pintype "input"))
      (node (ref "IC19") (pin "7") (pinfunction "VCCA_7") (pintype "power_in"))
      (node (ref "IC20") (pin "6") (pinfunction "ORG_6") (pintype "input"))
      (node (ref "IC20") (pin "8") (pinfunction "VCC_8") (pintype "power_in"))
      (node (ref "L22") (pin "1") (pinfunction "1_1") (pintype "passive"))
      (node (ref "L23") (pin "1") (pinfunction "1_1") (pintype "passive"))
      (node (ref "R187") (pin "1") (pinfunction "1_1") (pintype "passive"))
      (node (ref "R188") (pin "2") (pinfunction "2_2") (pintype "passive"))
      (node (ref "R189") (pin "2") (pinfunction "2_2") (pintype "passive"))
      (node (ref "R190") (pin "2") (pinfunction "2_2") (pintype "passive"))
      (node (ref "R191") (pin "2") (pinfunction "2_2") (pintype "passive"))
      (node (ref "R192") (pin "2") (pinfunction "2_2") (pintype "passive"))
      (node (ref "R193") (pin "2") (pinfunction "2_2") (pintype "passive"))
      (node (ref "R195") (pin "2") (pinfunction "2_2") (pintype "passive"))
    )
    (net (code "35") (name "unconnected-(D2-I{slash}O1-Pad1)") (class "Default")
      (node (ref "D2") (pin "1") (pinfunction "I/O1_1") (pintype "bidirectional+no_connect"))
    )
    (net (code "36") (name "unconnected-(D2-I{slash}O4-Pad6)") (class "Default")
      (node (ref "D2") (pin "6") (pinfunction "I/O4_6") (pintype "bidirectional+no_connect"))
    )
    (net (code "37") (name "unconnected-(IC17-ACBUS0-Pad26)") (class "Default")
      (node (ref "IC17") (pin "26") (pinfunction "ACBUS0_26") (pintype "bidirectional"))
    )
    (net (code "38") (name "unconnected-(IC17-ACBUS1-Pad27)") (class "Default")
      (node (ref "IC17") (pin "27") (pinfunction "ACBUS1_27") (pintype "bidirectional"))
    )
    (net (code "39") (name "unconnected-(IC17-ACBUS2-Pad28)") (class "Default")
      (node (ref "IC17") (pin "28") (pinfunction "ACBUS2_28") (pintype "bidirectional"))
    )
    (net (code "40") (name "unconnected-(IC17-ACBUS3-Pad29)") (class "Default")
      (node (ref "IC17") (pin "29") (pinfunction "ACBUS3_29") (pintype "bidirectional"))
    )
    (net (code "41") (name "unconnected-(IC17-ACBUS4-Pad30)") (class "Default")
      (node (ref "IC17") (pin "30") (pinfunction "ACBUS4_30") (pintype "bidirectional"))
    )
    (net (code "42") (name "unconnected-(IC17-ACBUS5-Pad32)") (class "Default")
      (node (ref "IC17") (pin "32") (pinfunction "ACBUS5_32") (pintype "bidirectional"))
    )
    (net (code "43") (name "unconnected-(IC17-ACBUS6-Pad33)") (class "Default")
      (node (ref "IC17") (pin "33") (pinfunction "ACBUS6_33") (pintype "bidirectional"))
    )
    (net (code "44") (name "unconnected-(IC17-ACBUS7-Pad34)") (class "Default")
      (node (ref "IC17") (pin "34") (pinfunction "ACBUS7_34") (pintype "bidirectional"))
    )
    (net (code "45") (name "unconnected-(IC17-ADBUS2-Pad18)") (class "Default")
      (node (ref "IC17") (pin "18") (pinfunction "ADBUS2_18") (pintype "bidirectional"))
    )
    (net (code "46") (name "unconnected-(IC17-ADBUS3-Pad19)") (class "Default")
      (node (ref "IC17") (pin "19") (pinfunction "ADBUS3_19") (pintype "bidirectional"))
    )
    (net (code "47") (name "unconnected-(IC17-ADBUS4-Pad21)") (class "Default")
      (node (ref "IC17") (pin "21") (pinfunction "ADBUS4_21") (pintype "bidirectional"))
    )
    (net (code "48") (name "unconnected-(IC17-ADBUS5-Pad22)") (class "Default")
      (node (ref "IC17") (pin "22") (pinfunction "ADBUS5_22") (pintype "bidirectional"))
    )
    (net (code "49") (name "unconnected-(IC17-ADBUS6-Pad23)") (class "Default")
      (node (ref "IC17") (pin "23") (pinfunction "ADBUS6_23") (pintype "bidirectional"))
    )
    (net (code "50") (name "unconnected-(IC17-ADBUS7-Pad24)") (class "Default")
      (node (ref "IC17") (pin "24") (pinfunction "ADBUS7_24") (pintype "bidirectional"))
    )
    (net (code "51") (name "unconnected-(IC17-BCBUS0-Pad48)") (class "Default")
      (node (ref "IC17") (pin "48") (pinfunction "BCBUS0_48") (pintype "bidirectional"))
    )
    (net (code "52") (name "unconnected-(IC17-BCBUS1-Pad52)") (class "Default")
      (node (ref "IC17") (pin "52") (pinfunction "BCBUS1_52") (pintype "bidirectional"))
    )
    (net (code "53") (name "unconnected-(IC17-BCBUS2-Pad53)") (class "Default")
      (node (ref "IC17") (pin "53") (pinfunction "BCBUS2_53") (pintype "bidirectional"))
    )
    (net (code "54") (name "unconnected-(IC17-BCBUS3-Pad54)") (class "Default")
      (node (ref "IC17") (pin "54") (pinfunction "BCBUS3_54") (pintype "bidirectional"))
    )
    (net (code "55") (name "unconnected-(IC17-BCBUS4-Pad55)") (class "Default")
      (node (ref "IC17") (pin "55") (pinfunction "BCBUS4_55") (pintype "bidirectional"))
    )
    (net (code "56") (name "unconnected-(IC17-BCBUS5-Pad57)") (class "Default")
      (node (ref "IC17") (pin "57") (pinfunction "BCBUS5_57") (pintype "bidirectional"))
    )
    (net (code "57") (name "unconnected-(IC17-BCBUS6-Pad58)") (class "Default")
      (node (ref "IC17") (pin "58") (pinfunction "BCBUS6_58") (pintype "bidirectional"))
    )
    (net (code "58") (name "unconnected-(IC17-BDBUS4-Pad43)") (class "Default")
      (node (ref "IC17") (pin "43") (pinfunction "BDBUS4_43") (pintype "bidirectional"))
    )
    (net (code "59") (name "unconnected-(IC17-BDBUS5-Pad44)") (class "Default")
      (node (ref "IC17") (pin "44") (pinfunction "BDBUS5_44") (pintype "bidirectional"))
    )
    (net (code "60") (name "unconnected-(IC17-BDBUS6-Pad45)") (class "Default")
      (node (ref "IC17") (pin "45") (pinfunction "BDBUS6_45") (pintype "bidirectional"))
    )
    (net (code "61") (name "unconnected-(IC17-BDBUS7-Pad46)") (class "Default")
      (node (ref "IC17") (pin "46") (pinfunction "BDBUS7_46") (pintype "bidirectional"))
    )
    (net (code "62") (name "unconnected-(IC17-GND-Pad65)") (class "Default")
      (node (ref "IC17") (pin "65") (pinfunction "GND_65") (pintype "power_in"))
    )
    (net (code "63") (name "unconnected-(IC17-PWREN#-Pad60)") (class "Default")
      (node (ref "IC17") (pin "60") (pinfunction "PWREN#_60") (pintype "output"))
    )
    (net (code "64") (name "unconnected-(IC17-SUSPEND#-Pad36)") (class "Default")
      (node (ref "IC17") (pin "36") (pinfunction "SUSPEND#_36") (pintype "output"))
    )
    (net (code "65") (name "unconnected-(J23-ID-Pad4)") (class "Default")
      (node (ref "J23") (pin "4") (pinfunction "ID_4") (pintype "passive+no_connect"))
    )
  )
)
